# Tx_555_Sch.net
KiCad netlist of a schematic drawn in Altium Designer
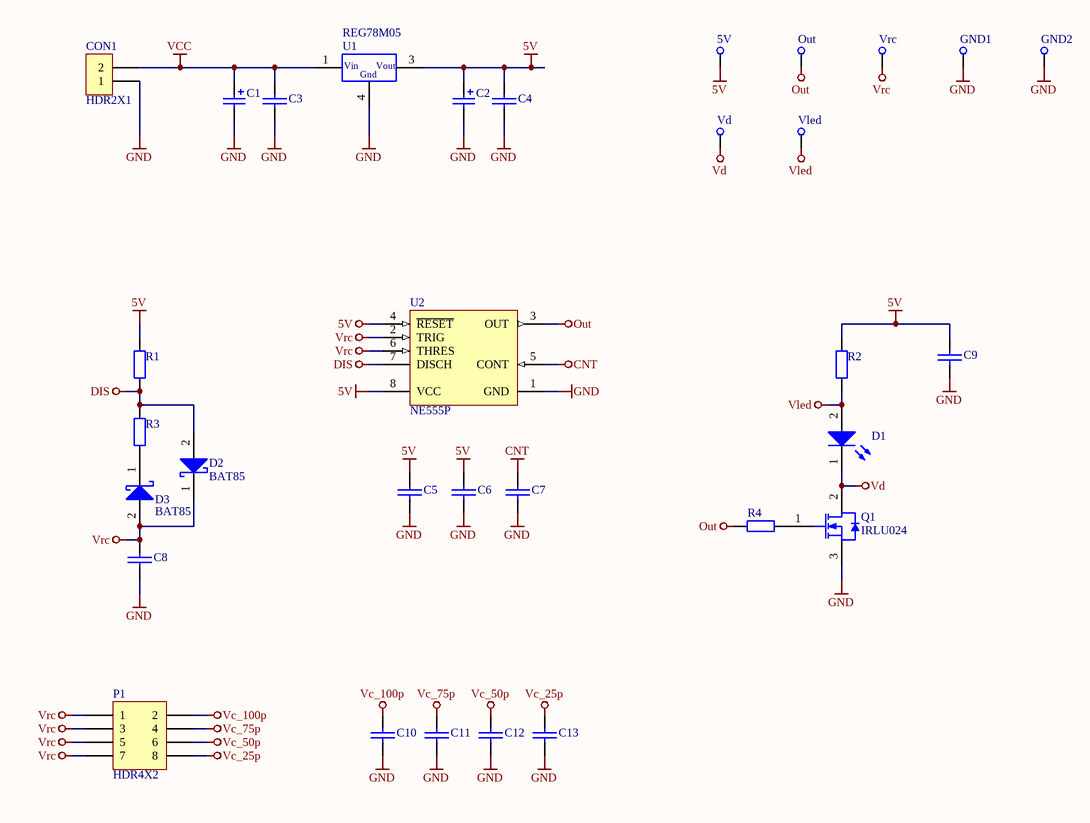
[diagram p0: Tx_555_Sch.SchDoc]

(export (version "E")
  (design (tool "Eeschema 10.0.6"))
  (components
    (comp (ref "5V")
      (value "TP TH")
      (footprint "TP_TH_2.5mm")
      (fields (field (name "SOURCE") "UoAPE_Connectors and Mechanical.SchLib"))
      (libsource (lib "ECSE@UoA") (part "TP TH"))
    )
    (comp (ref "C1") (value "ECAP") (footprint "CR05") (libsource (lib "ECSE@UoA") (part "ECAP")))
    (comp (ref "C2") (value "ECAP") (footprint "CR05") (libsource (lib "ECSE@UoA") (part "ECAP")))
    (comp (ref "C3")
      (value "CCAP_TH_5P0")
      (footprint "CCAP_5P0")
      (description "TH ceramic cap with 5mm pitch")
      (libsource (lib "ECSE@UoA") (part "Symbol"))
    )
    (comp (ref "C4")
      (value "CCAP_TH_5P0")
      (footprint "CCAP_5P0")
      (description "TH ceramic cap with 5mm pitch")
      (libsource (lib "ECSE@UoA") (part "Symbol"))
    )
    (comp (ref "C5")
      (value "CCAP_TH_5P0")
      (footprint "CCAP_5P0")
      (description "TH ceramic cap with 5mm pitch")
      (libsource (lib "ECSE@UoA") (part "Symbol"))
    )
    (comp (ref "C6")
      (value "CCAP_TH_5P0")
      (footprint "CCAP_5P0")
      (description "TH ceramic cap with 5mm pitch")
      (libsource (lib "ECSE@UoA") (part "Symbol"))
    )
    (comp (ref "C7")
      (value "CCAP_TH_5P0")
      (footprint "CCAP_5P0")
      (description "TH ceramic cap with 5mm pitch")
      (libsource (lib "ECSE@UoA") (part "Symbol"))
    )
    (comp (ref "C8")
      (value "CCAP_TH_5P0")
      (footprint "CCAP_5P0")
      (description "TH ceramic cap with 5mm pitch")
      (libsource (lib "ECSE@UoA") (part "Symbol"))
    )
    (comp (ref "C9")
      (value "CCAP_TH_5P0")
      (footprint "CCAP_5P0")
      (description "TH ceramic cap with 5mm pitch")
      (libsource (lib "ECSE@UoA") (part "Symbol"))
    )
    (comp (ref "C10")
      (value "CCAP_TH_5P0")
      (footprint "CCAP_5P0")
      (description "TH ceramic cap with 5mm pitch")
      (libsource (lib "ECSE@UoA") (part "Symbol"))
    )
    (comp (ref "C11")
      (value "CCAP_TH_5P0")
      (footprint "CCAP_5P0")
      (description "TH ceramic cap with 5mm pitch")
      (libsource (lib "ECSE@UoA") (part "Symbol"))
    )
    (comp (ref "C12")
      (value "CCAP_TH_5P0")
      (footprint "CCAP_5P0")
      (description "TH ceramic cap with 5mm pitch")
      (libsource (lib "ECSE@UoA") (part "Symbol"))
    )
    (comp (ref "C13")
      (value "CCAP_TH_5P0")
      (footprint "CCAP_5P0")
      (description "TH ceramic cap with 5mm pitch")
      (libsource (lib "ECSE@UoA") (part "Symbol"))
    )
    (comp (ref "CON1")
      (value "HDR2X1")
      (footprint "HDR2X1_2P54")
      (description "Header 2X1")
      (libsource (lib "ECSE@UoA") (part "HDR2X1"))
    )
    (comp (ref "D1")
      (value "LED_TH")
      (footprint "TH_LED")
      (description "LED RED TH")
      (libsource (lib "ECSE@UoA") (part "8706943c75ba83719d021d2fdc84c58"))
    )
    (comp (ref "D2")
      (value "BAT85")
      (footprint "FP-SOD68-MFG")
      (description "Rectifier Diode, Schottky, 1 Phase, 1 Element, 0.2A, 30V V(RRM), Silicon, DO-34")
      (libsource (lib "ECSE@UoA") (part "1d6ec82d83fb6aee721767c19dac4b9"))
    )
    (comp (ref "D3")
      (value "BAT85")
      (footprint "FP-SOD68-MFG")
      (description "Rectifier Diode, Schottky, 1 Phase, 1 Element, 0.2A, 30V V(RRM), Silicon, DO-34")
      (libsource (lib "ECSE@UoA") (part "1d6ec82d83fb6aee721767c19dac4b9"))
    )
    (comp (ref "GND1")
      (value "TP TH")
      (footprint "TP_TH_2.5mm")
      (fields (field (name "SOURCE") "UoAPE_Connectors and Mechanical.SchLib"))
      (libsource (lib "ECSE@UoA") (part "TP TH"))
    )
    (comp (ref "GND2")
      (value "TP TH")
      (footprint "TP_TH_2.5mm")
      (fields (field (name "SOURCE") "UoAPE_Connectors and Mechanical.SchLib"))
      (libsource (lib "ECSE@UoA") (part "TP TH"))
    )
    (comp (ref "Out")
      (value "TP TH")
      (footprint "TP_TH_2.5mm")
      (fields (field (name "SOURCE") "UoAPE_Connectors and Mechanical.SchLib"))
      (libsource (lib "ECSE@UoA") (part "TP TH"))
    )
    (comp (ref "P1")
      (value "HDR4X2")
      (footprint "HDR4X2-2P54")
      (description "Header, 8-Pin, Dual row")
      (libsource (lib "ECSE@UoA") (part "HDR4x2"))
    )
    (comp (ref "Q1")
      (value "IRLU024")
      (footprint "FP-PG-TO251-3-MFG")
      (libsource (lib "ECSE@UoA") (part "535c4fe1372f32a24686ada0a8c11ba"))
    )
    (comp (ref "R1")
      (value "RESAX4")
      (footprint "RAX4")
      (description "Axial Resistor")
      (libsource (lib "") (part "Symbol_2"))
    )
    (comp (ref "R2")
      (value "RESAX4")
      (footprint "RAX4")
      (description "Axial Resistor")
      (libsource (lib "") (part "Symbol_2"))
    )
    (comp (ref "R3")
      (value "RESAX4")
      (footprint "RAX4")
      (description "Axial Resistor")
      (libsource (lib "") (part "Symbol_2"))
    )
    (comp (ref "R4")
      (value "RESAX4")
      (footprint "RAX4")
      (description "Axial Resistor")
      (libsource (lib "") (part "Symbol_1"))
    )
    (comp (ref "U1")
      (value "REG78M05")
      (footprint "TO220_Reg")
      (description "78M Series Linear Regulators")
      (libsource (lib "ECSE@UoA") (part "REG78MXX"))
    )
    (comp (ref "U2")
      (value "NE555P")
      (footprint "P0008A")
      (description "1 Func, BIPolar, PDIP8")
      (libsource (lib "ECSE@UoA") (part "TI-NE555-P8"))
    )
    (comp (ref "Vd")
      (value "TP TH")
      (footprint "TP_TH_2.5mm")
      (fields (field (name "SOURCE") "UoAPE_Connectors and Mechanical.SchLib"))
      (libsource (lib "ECSE@UoA") (part "TP TH"))
    )
    (comp (ref "Vled")
      (value "TP TH")
      (footprint "TP_TH_2.5mm")
      (fields (field (name "SOURCE") "UoAPE_Connectors and Mechanical.SchLib"))
      (libsource (lib "ECSE@UoA") (part "TP TH"))
    )
    (comp (ref "Vrc")
      (value "TP TH")
      (footprint "TP_TH_2.5mm")
      (fields (field (name "SOURCE") "UoAPE_Connectors and Mechanical.SchLib"))
      (libsource (lib "ECSE@UoA") (part "TP TH"))
    )
  )
  (nets
    (net (code "1") (name "5V") (class "Default")
      (node (ref "5V") (pin "1") (pinfunction "1_1") (pintype "passive"))
      (node (ref "C2") (pin "1") (pinfunction "1_1") (pintype "passive"))
      (node (ref "C4") (pin "2") (pinfunction "2_2") (pintype "passive"))
      (node (ref "C5") (pin "2") (pinfunction "2_2") (pintype "passive"))
      (node (ref "C6") (pin "2") (pinfunction "2_2") (pintype "passive"))
      (node (ref "C9") (pin "2") (pinfunction "2_2") (pintype "passive"))
      (node (ref "R1") (pin "2") (pinfunction "2_2") (pintype "passive"))
      (node (ref "R2") (pin "2") (pinfunction "2_2") (pintype "passive"))
      (node (ref "U1") (pin "3") (pinfunction "Vout_3") (pintype "passive"))
      (node (ref "U2") (pin "4") (pinfunction "~{RESET}_4") (pintype "input"))
      (node (ref "U2") (pin "8") (pinfunction "VCC_8") (pintype "power_in"))
    )
    (net (code "2") (name "CNT") (class "Default")
      (node (ref "C7") (pin "2") (pinfunction "2_2") (pintype "passive"))
      (node (ref "U2") (pin "5") (pinfunction "CONT_5") (pintype "input"))
    )
    (net (code "3") (name "DIS") (class "Default")
      (node (ref "D2") (pin "2") (pinfunction "A_2") (pintype "passive"))
      (node (ref "R1") (pin "1") (pinfunction "1_1") (pintype "passive"))
      (node (ref "R3") (pin "2") (pinfunction "2_2") (pintype "passive"))
      (node (ref "U2") (pin "7") (pinfunction "DISCH_7") (pintype "open_collector"))
    )
    (net (code "4") (name "GND") (class "Default")
      (node (ref "C1") (pin "2") (pinfunction "2_2") (pintype "passive"))
      (node (ref "C10") (pin "1") (pinfunction "1_1") (pintype "passive"))
      (node (ref "C11") (pin "1") (pinfunction "1_1") (pintype "passive"))
      (node (ref "C12") (pin "1") (pinfunction "1_1") (pintype "passive"))
      (node (ref "C13") (pin "1") (pinfunction "1_1") (pintype "passive"))
      (node (ref "C2") (pin "2") (pinfunction "2_2") (pintype "passive"))
      (node (ref "C3") (pin "1") (pinfunction "1_1") (pintype "passive"))
      (node (ref "C4") (pin "1") (pinfunction "1_1") (pintype "passive"))
      (node (ref "C5") (pin "1") (pinfunction "1_1") (pintype "passive"))
      (node (ref "C6") (pin "1") (pinfunction "1_1") (pintype "passive"))
      (node (ref "C7") (pin "1") (pinfunction "1_1") (pintype "passive"))
      (node (ref "C8") (pin "1") (pinfunction "1_1") (pintype "passive"))
      (node (ref "C9") (pin "1") (pinfunction "1_1") (pintype "passive"))
      (node (ref "CON1") (pin "1") (pinfunction "1_1") (pintype "passive"))
      (node (ref "GND1") (pin "1") (pinfunction "1_1") (pintype "passive"))
      (node (ref "GND2") (pin "1") (pinfunction "1_1") (pintype "passive"))
      (node (ref "Q1") (pin "3") (pinfunction "SOURCE_3") (pintype "passive"))
      (node (ref "U1") (pin "4") (pinfunction "Gnd_4") (pintype "passive"))
      (node (ref "U2") (pin "1") (pinfunction "GND_1") (pintype "power_in"))
    )
    (net (code "5") (name "Net-(D3-C)") (class "Default")
      (node (ref "D3") (pin "1") (pinfunction "C_1") (pintype "passive"))
      (node (ref "R3") (pin "1") (pinfunction "1_1") (pintype "passive"))
    )
    (net (code "6") (name "Net-(Q1-GATE)") (class "Default")
      (node (ref "Q1") (pin "1") (pinfunction "GATE_1") (pintype "passive"))
      (node (ref "R4") (pin "1") (pinfunction "1_1") (pintype "passive"))
    )
    (net (code "7") (name "Out") (class "Default")
      (node (ref "Out") (pin "1") (pinfunction "1_1") (pintype "passive"))
      (node (ref "R4") (pin "2") (pinfunction "2_2") (pintype "passive"))
      (node (ref "U2") (pin "3") (pinfunction "OUT_3") (pintype "output"))
    )
    (net (code "8") (name "VCC") (class "Default")
      (node (ref "C1") (pin "1") (pinfunction "1_1") (pintype "passive"))
      (node (ref "C3") (pin "2") (pinfunction "2_2") (pintype "passive"))
      (node (ref "CON1") (pin "2") (pinfunction "2_2") (pintype "passive"))
      (node (ref "U1") (pin "1") (pinfunction "Vin_1") (pintype "passive"))
    )
    (net (code "9") (name "Vc_25p") (class "Default")
      (node (ref "C13") (pin "2") (pinfunction "2_2") (pintype "passive"))
      (node (ref "P1") (pin "8") (pinfunction "8_8") (pintype "passive"))
    )
    (net (code "10") (name "Vc_50p") (class "Default")
      (node (ref "C12") (pin "2") (pinfunction "2_2") (pintype "passive"))
      (node (ref "P1") (pin "6") (pinfunction "6_6") (pintype "passive"))
    )
    (net (code "11") (name "Vc_75p") (class "Default")
      (node (ref "C11") (pin "2") (pinfunction "2_2") (pintype "passive"))
      (node (ref "P1") (pin "4") (pinfunction "4_4") (pintype "passive"))
    )
    (net (code "12") (name "Vc_100p") (class "Default")
      (node (ref "C10") (pin "2") (pinfunction "2_2") (pintype "passive"))
      (node (ref "P1") (pin "2") (pinfunction "2_2") (pintype "passive"))
    )
    (net (code "13") (name "Vd") (class "Default")
      (node (ref "D1") (pin "1") (pinfunction "C_1") (pintype "passive"))
      (node (ref "Q1") (pin "2") (pinfunction "DRAIN_2") (pintype "passive"))
      (node (ref "Vd") (pin "1") (pinfunction "1_1") (pintype "passive"))
    )
    (net (code "14") (name "Vled") (class "Default")
      (node (ref "D1") (pin "2") (pinfunction "A_2") (pintype "passive"))
      (node (ref "R2") (pin "1") (pinfunction "1_1") (pintype "passive"))
      (node (ref "Vled") (pin "1") (pinfunction "1_1") (pintype "passive"))
    )
    (net (code "15") (name "Vrc") (class "Default")
      (node (ref "C8") (pin "2") (pinfunction "2_2") (pintype "passive"))
      (node (ref "D2") (pin "1") (pinfunction "C_1") (pintype "passive"))
      (node (ref "D3") (pin "2") (pinfunction "A_2") (pintype "passive"))
      (node (ref "P1") (pin "1") (pinfunction "1_1") (pintype "passive"))
      (node (ref "P1") (pin "3") (pinfunction "3_3") (pintype "passive"))
      (node (ref "P1") (pin "5") (pinfunction "5_5") (pintype "passive"))
      (node (ref "P1") (pin "7") (pinfunction "7_7") (pintype "passive"))
      (node (ref "U2") (pin "2") (pinfunction "TRIG_2") (pintype "input"))
      (node (ref "U2") (pin "6") (pinfunction "THRES_6") (pintype "input"))
      (node (ref "Vrc") (pin "1") (pinfunction "1_1") (pintype "passive"))
    )
  )
)
